# Sheet1.net
KiCad netlist of a schematic drawn in Altium Designer
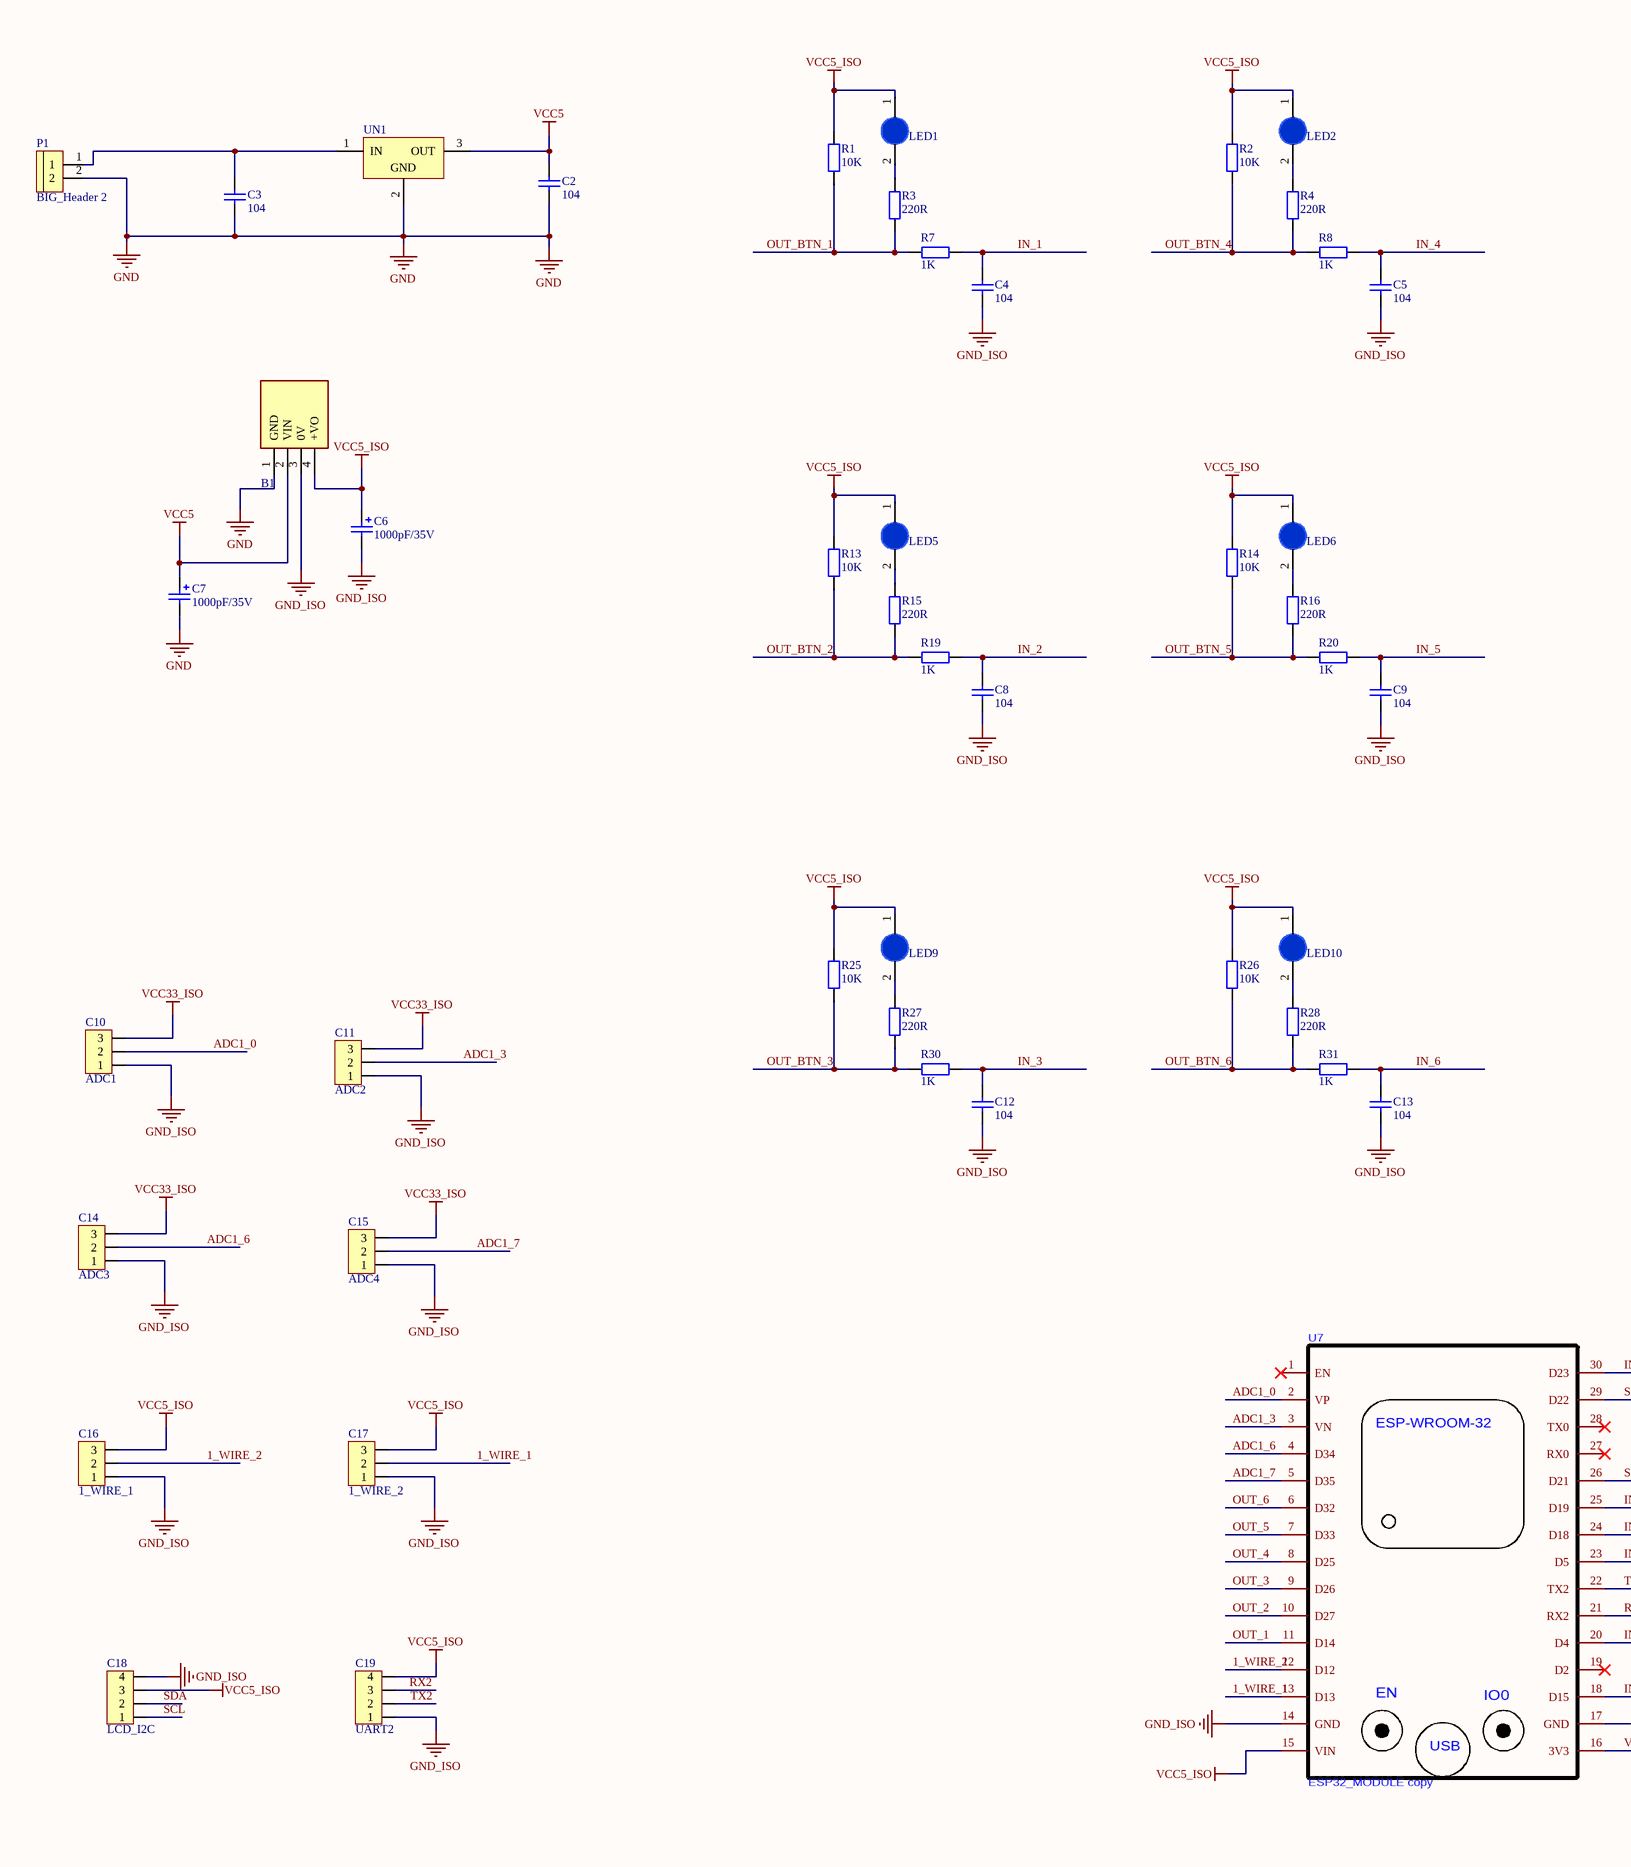
[diagram p0: Sheet1.SchDoc, left]
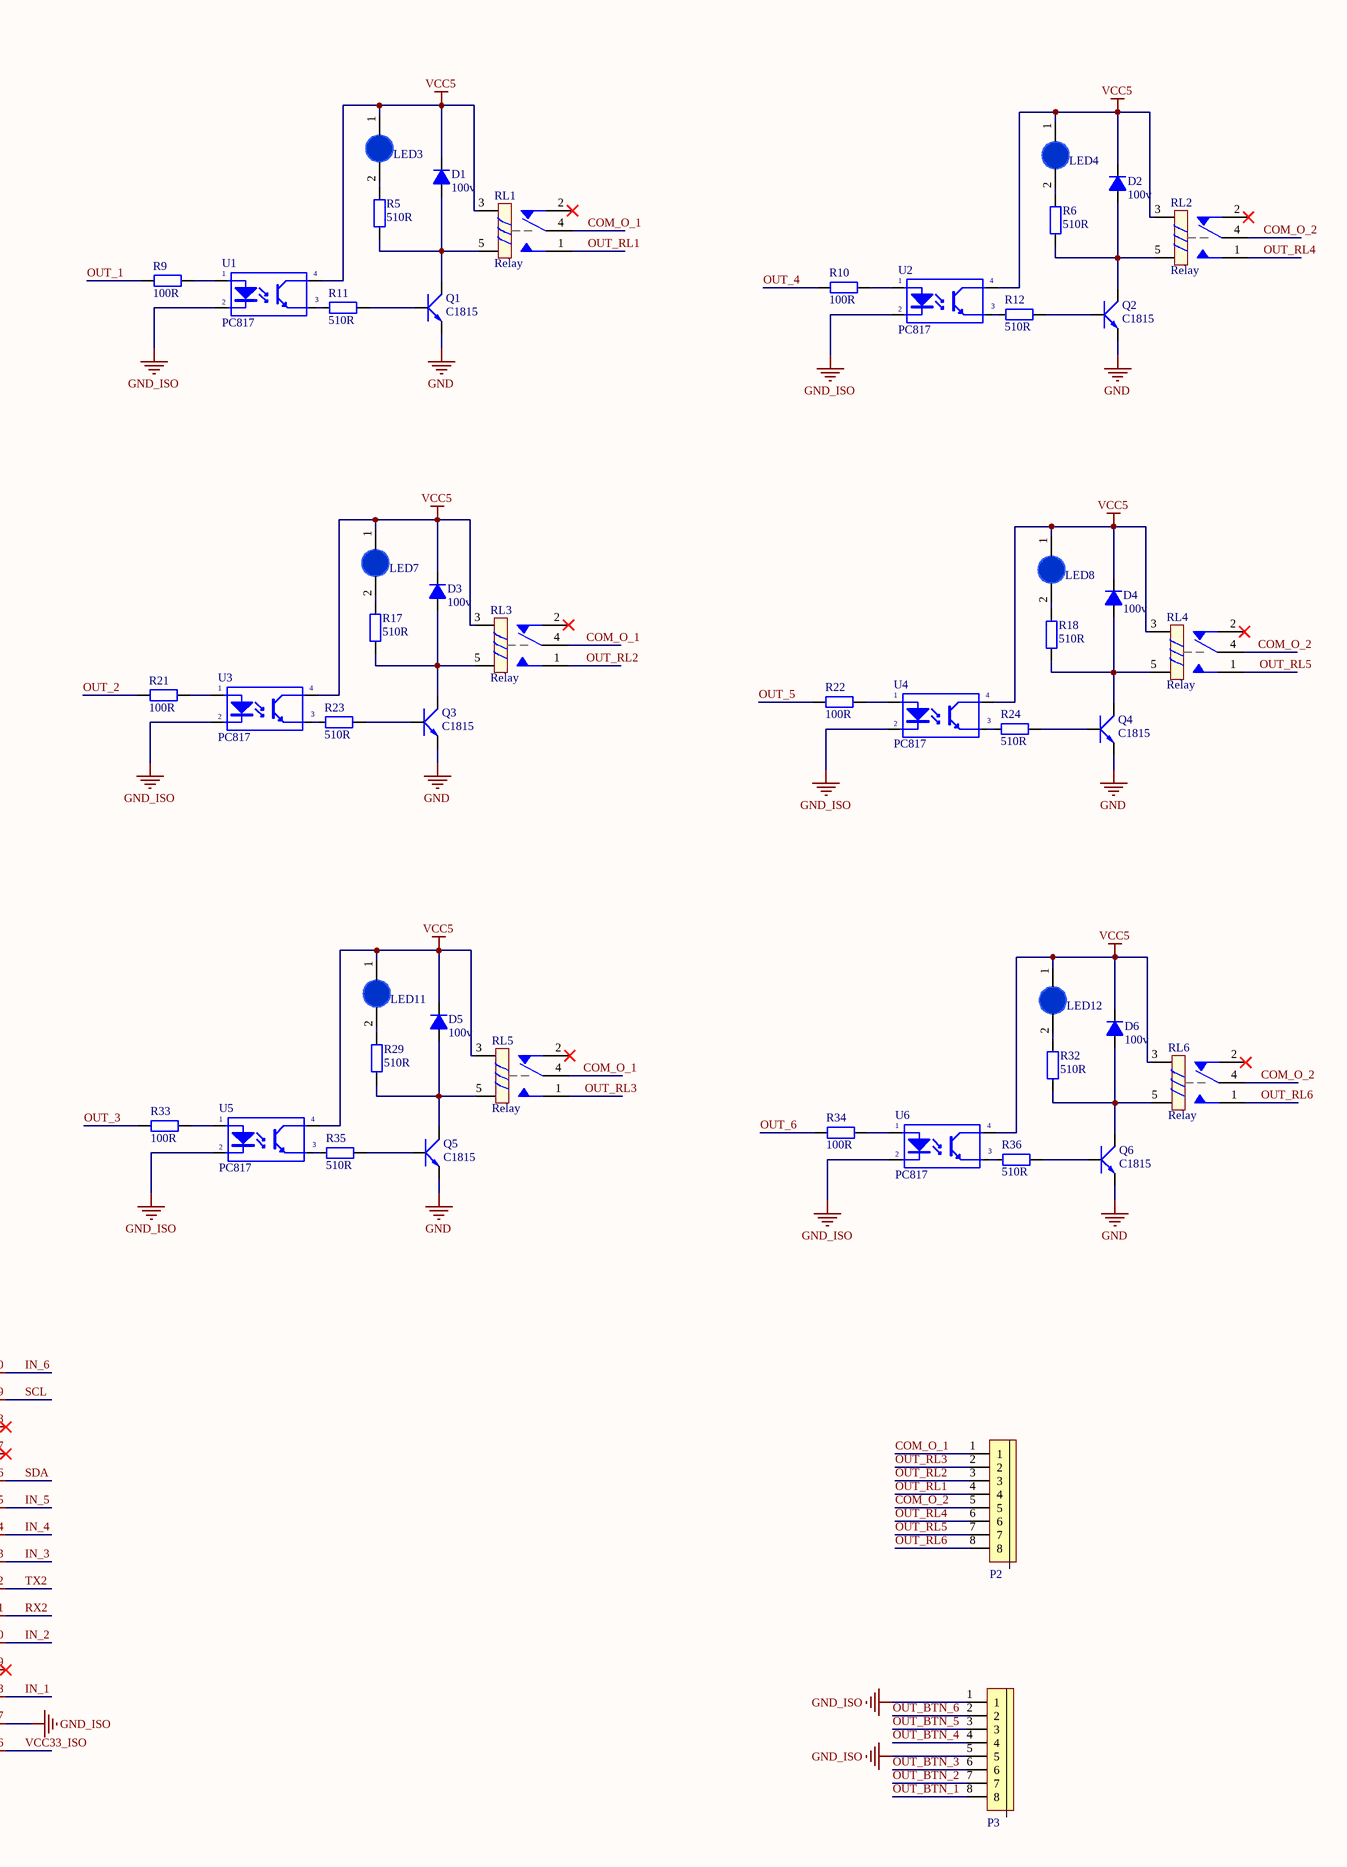
[diagram p1: Sheet1.SchDoc, right]

(export (version "E")
  (design (tool "Eeschema 10.0.6"))
  (components
    (comp (ref "B1")
      (value "B0505S1W")
      (footprint "B0505S1W")
      (description "Power Supply")
      (fields (field (name "MANUFACTURER_PART_NUMBER") "B0505S-1W"))
      (libsource (lib "myLib_v1") (part "B0505S1W"))
    )
    (comp (ref "C2")
      (value "104")
      (footprint "tu gom")
      (description "Cắm")
      (libsource (lib "Altium_Lib_by_KhueNguyenCreator") (part "Tu gom 104 50V"))
    )
    (comp (ref "C3")
      (value "104")
      (footprint "tu gom")
      (description "Cắm")
      (libsource (lib "Altium_Lib_by_KhueNguyenCreator") (part "Tu gom 104 50V"))
    )
    (comp (ref "C4")
      (value "104")
      (footprint "tu gom")
      (description "Cắm")
      (libsource (lib "Altium_Lib_by_KhueNguyenCreator") (part "Tu gom 104 50V"))
    )
    (comp (ref "C5")
      (value "104")
      (footprint "tu gom")
      (description "Cắm")
      (libsource (lib "Altium_Lib_by_KhueNguyenCreator") (part "Tu gom 104 50V"))
    )
    (comp (ref "C6")
      (value "1000pF/35V")
      (footprint "CP2/5")
      (description "Polarized Capacitor (Surface Mount)")
      (fields (field (name "Comment") "Cap Pol3") (field (name "PUBLISHER") "Altium Limited"))
      (libsource (lib "myLib_v1") (part "Cap Pol3"))
    )
    (comp (ref "C7")
      (value "1000pF/35V")
      (footprint "CP2/5")
      (description "Polarized Capacitor (Surface Mount)")
      (fields (field (name "Comment") "Cap Pol3") (field (name "PUBLISHER") "Altium Limited"))
      (libsource (lib "myLib_v1") (part "Cap Pol3"))
    )
    (comp (ref "C8")
      (value "104")
      (footprint "tu gom")
      (description "Cắm")
      (libsource (lib "Altium_Lib_by_KhueNguyenCreator") (part "Tu gom 104 50V"))
    )
    (comp (ref "C9")
      (value "104")
      (footprint "tu gom")
      (description "Cắm")
      (libsource (lib "Altium_Lib_by_KhueNguyenCreator") (part "Tu gom 104 50V"))
    )
    (comp (ref "C10")
      (value "ADC1")
      (footprint "Header3")
      (description "Header IDC, 3 x 1 Pin Vertical 2.54mm Pitch (Non-Boxed, Male)")
      (fields
        (field (name "MANUFACTURER") "Würth Elektronik eiSos GmbH")
        (field (name "PARTNO") "613002143121")
        (field (name "CREATED BY") "Karrer Zheng")
      )
      (libsource (lib "myLib_v1") (part "Header3"))
    )
    (comp (ref "C11")
      (value "ADC2")
      (footprint "Header3")
      (description "Header IDC, 3 x 1 Pin Vertical 2.54mm Pitch (Non-Boxed, Male)")
      (fields
        (field (name "MANUFACTURER") "Würth Elektronik eiSos GmbH")
        (field (name "PARTNO") "613002143121")
        (field (name "CREATED BY") "Karrer Zheng")
      )
      (libsource (lib "myLib_v1") (part "Header3"))
    )
    (comp (ref "C12")
      (value "104")
      (footprint "tu gom")
      (description "Cắm")
      (libsource (lib "Altium_Lib_by_KhueNguyenCreator") (part "Tu gom 104 50V"))
    )
    (comp (ref "C13")
      (value "104")
      (footprint "tu gom")
      (description "Cắm")
      (libsource (lib "Altium_Lib_by_KhueNguyenCreator") (part "Tu gom 104 50V"))
    )
    (comp (ref "C14")
      (value "ADC3")
      (footprint "Header3")
      (description "Header IDC, 3 x 1 Pin Vertical 2.54mm Pitch (Non-Boxed, Male)")
      (fields
        (field (name "MANUFACTURER") "Würth Elektronik eiSos GmbH")
        (field (name "PARTNO") "613002143121")
        (field (name "CREATED BY") "Karrer Zheng")
      )
      (libsource (lib "myLib_v1") (part "Header3"))
    )
    (comp (ref "C15")
      (value "ADC4")
      (footprint "Header3")
      (description "Header IDC, 3 x 1 Pin Vertical 2.54mm Pitch (Non-Boxed, Male)")
      (fields
        (field (name "MANUFACTURER") "Würth Elektronik eiSos GmbH")
        (field (name "PARTNO") "613002143121")
        (field (name "CREATED BY") "Karrer Zheng")
      )
      (libsource (lib "myLib_v1") (part "Header3"))
    )
    (comp (ref "C16")
      (value "1_WIRE_1")
      (footprint "Header3")
      (description "Header IDC, 3 x 1 Pin Vertical 2.54mm Pitch (Non-Boxed, Male)")
      (fields
        (field (name "MANUFACTURER") "Würth Elektronik eiSos GmbH")
        (field (name "PARTNO") "613002143121")
        (field (name "CREATED BY") "Karrer Zheng")
      )
      (libsource (lib "myLib_v1") (part "Header3"))
    )
    (comp (ref "C17")
      (value "1_WIRE_2")
      (footprint "Header3")
      (description "Header IDC, 3 x 1 Pin Vertical 2.54mm Pitch (Non-Boxed, Male)")
      (fields
        (field (name "MANUFACTURER") "Würth Elektronik eiSos GmbH")
        (field (name "PARTNO") "613002143121")
        (field (name "CREATED BY") "Karrer Zheng")
      )
      (libsource (lib "myLib_v1") (part "Header3"))
    )
    (comp (ref "C18")
      (value "LCD_I2C")
      (footprint "Header4")
      (description "Header IDC, 4 x 1 Pin Vertical 2.54mm Pitch (Non-Boxed, Male)")
      (fields
        (field (name "MANUFACTURER") "Würth Elektronik eiSos GmbH")
        (field (name "PARTNO") "613002143121")
        (field (name "CREATED BY") "Karrer Zheng")
      )
      (libsource (lib "myLib_v1") (part "Header4"))
    )
    (comp (ref "C19")
      (value "UART2")
      (footprint "Header4")
      (description "Header IDC, 4 x 1 Pin Vertical 2.54mm Pitch (Non-Boxed, Male)")
      (fields
        (field (name "MANUFACTURER") "Würth Elektronik eiSos GmbH")
        (field (name "PARTNO") "613002143121")
        (field (name "CREATED BY") "Karrer Zheng")
      )
      (libsource (lib "myLib_v1") (part "Header4"))
    )
    (comp (ref "D1")
      (value "100v")
      (footprint "DIODE 0.5A")
      (description "Cắm")
      (libsource (lib "Altium_Lib_by_KhueNguyenCreator") (part "Diode 1N4148"))
    )
    (comp (ref "D2")
      (value "100v")
      (footprint "DIODE 0.5A")
      (description "Cắm")
      (libsource (lib "Altium_Lib_by_KhueNguyenCreator") (part "Diode 1N4148"))
    )
    (comp (ref "D3")
      (value "100v")
      (footprint "DIODE 0.5A")
      (description "Cắm")
      (libsource (lib "Altium_Lib_by_KhueNguyenCreator") (part "Diode 1N4148"))
    )
    (comp (ref "D4")
      (value "100v")
      (footprint "DIODE 0.5A")
      (description "Cắm")
      (libsource (lib "Altium_Lib_by_KhueNguyenCreator") (part "Diode 1N4148"))
    )
    (comp (ref "D5")
      (value "100v")
      (footprint "DIODE 0.5A")
      (description "Cắm")
      (libsource (lib "Altium_Lib_by_KhueNguyenCreator") (part "Diode 1N4148"))
    )
    (comp (ref "D6")
      (value "100v")
      (footprint "DIODE 0.5A")
      (description "Cắm")
      (libsource (lib "Altium_Lib_by_KhueNguyenCreator") (part "Diode 1N4148"))
    )
    (comp (ref "LED1")
      (value "LED 3mm")
      (footprint "LED-3MM-BLUE")
      (description "Cắm")
      (libsource (lib "myLib_v1") (part "LED 3mm Xanh Duong"))
    )
    (comp (ref "LED2")
      (value "LED 3mm")
      (footprint "LED-3MM-BLUE")
      (description "Cắm")
      (libsource (lib "myLib_v1") (part "LED 3mm Xanh Duong"))
    )
    (comp (ref "LED3")
      (value "LED 3mm")
      (footprint "LED-3MM-BLUE")
      (description "Cắm")
      (libsource (lib "myLib_v1") (part "LED 3mm Xanh Duong"))
    )
    (comp (ref "LED4")
      (value "LED 3mm")
      (footprint "LED-3MM-BLUE")
      (description "Cắm")
      (libsource (lib "myLib_v1") (part "LED 3mm Xanh Duong"))
    )
    (comp (ref "LED5")
      (value "LED 3mm")
      (footprint "LED-3MM-BLUE")
      (description "Cắm")
      (libsource (lib "myLib_v1") (part "LED 3mm Xanh Duong"))
    )
    (comp (ref "LED6")
      (value "LED 3mm")
      (footprint "LED-3MM-BLUE")
      (description "Cắm")
      (libsource (lib "myLib_v1") (part "LED 3mm Xanh Duong"))
    )
    (comp (ref "LED7")
      (value "LED 3mm")
      (footprint "LED-3MM-BLUE")
      (description "Cắm")
      (libsource (lib "myLib_v1") (part "LED 3mm Xanh Duong"))
    )
    (comp (ref "LED8")
      (value "LED 3mm")
      (footprint "LED-3MM-BLUE")
      (description "Cắm")
      (libsource (lib "myLib_v1") (part "LED 3mm Xanh Duong"))
    )
    (comp (ref "LED9")
      (value "LED 3mm")
      (footprint "LED-3MM-BLUE")
      (description "Cắm")
      (libsource (lib "myLib_v1") (part "LED 3mm Xanh Duong"))
    )
    (comp (ref "LED10")
      (value "LED 3mm")
      (footprint "LED-3MM-BLUE")
      (description "Cắm")
      (libsource (lib "myLib_v1") (part "LED 3mm Xanh Duong"))
    )
    (comp (ref "LED11")
      (value "LED 3mm")
      (footprint "LED-3MM-BLUE")
      (description "Cắm")
      (libsource (lib "myLib_v1") (part "LED 3mm Xanh Duong"))
    )
    (comp (ref "LED12")
      (value "LED 3mm")
      (footprint "LED-3MM-BLUE")
      (description "Cắm")
      (libsource (lib "myLib_v1") (part "LED 3mm Xanh Duong"))
    )
    (comp (ref "P1")
      (value "BIG_Header 2")
      (footprint "BIG_Header 2")
      (libsource (lib "BYTECH_HW_LIB_2019 (1)") (part "BIG_Header 2"))
    )
    (comp (ref "P2")
      (value "BIG Heager 8")
      (footprint "BIG_Header 8")
      (libsource (lib "BYTECH_HW_LIB_2019 (1)") (part "BIG_Header 8"))
    )
    (comp (ref "P3")
      (value "BIG Heager 8")
      (footprint "BIG_Header 8")
      (libsource (lib "BYTECH_HW_LIB_2019 (1)") (part "BIG_Header 8"))
    )
    (comp (ref "Q1")
      (value "C1815")
      (footprint "C1815_cam")
      (description "NPN 600mW, ECB")
      (libsource (lib "myLib_v1") (part "C1815"))
    )
    (comp (ref "Q2")
      (value "C1815")
      (footprint "C1815_cam")
      (description "NPN 600mW, ECB")
      (libsource (lib "myLib_v1") (part "C1815"))
    )
    (comp (ref "Q3")
      (value "C1815")
      (footprint "C1815_cam")
      (description "NPN 600mW, ECB")
      (libsource (lib "myLib_v1") (part "C1815"))
    )
    (comp (ref "Q4")
      (value "C1815")
      (footprint "C1815_cam")
      (description "NPN 600mW, ECB")
      (libsource (lib "myLib_v1") (part "C1815"))
    )
    (comp (ref "Q5")
      (value "C1815")
      (footprint "C1815_cam")
      (description "NPN 600mW, ECB")
      (libsource (lib "myLib_v1") (part "C1815"))
    )
    (comp (ref "Q6")
      (value "C1815")
      (footprint "C1815_cam")
      (description "NPN 600mW, ECB")
      (libsource (lib "myLib_v1") (part "C1815"))
    )
    (comp (ref "R1")
      (value "10K")
      (footprint "R1/4W")
      (description "Resistor 1/4W")
      (libsource (lib "myLib_v1") (part "R1/4W"))
    )
    (comp (ref "R2")
      (value "10K")
      (footprint "R1/4W")
      (description "Resistor 1/4W")
      (libsource (lib "myLib_v1") (part "R1/4W"))
    )
    (comp (ref "R3")
      (value "220R")
      (footprint "R1/4W")
      (description "Resistor 1/4W")
      (libsource (lib "myLib_v1") (part "R1/4W"))
    )
    (comp (ref "R4")
      (value "220R")
      (footprint "R1/4W")
      (description "Resistor 1/4W")
      (libsource (lib "myLib_v1") (part "R1/4W"))
    )
    (comp (ref "R5")
      (value "510R")
      (footprint "R1/4W")
      (description "Resistor 1/4W")
      (libsource (lib "myLib_v1") (part "R1/4W"))
    )
    (comp (ref "R6")
      (value "510R")
      (footprint "R1/4W")
      (description "Resistor 1/4W")
      (libsource (lib "myLib_v1") (part "R1/4W"))
    )
    (comp (ref "R7")
      (value "1K")
      (footprint "R1/4W")
      (description "Resistor 1/4W")
      (libsource (lib "myLib_v1") (part "R1/4W"))
    )
    (comp (ref "R8")
      (value "1K")
      (footprint "R1/4W")
      (description "Resistor 1/4W")
      (libsource (lib "myLib_v1") (part "R1/4W"))
    )
    (comp (ref "R9")
      (value "100R")
      (footprint "R1/4W")
      (description "Resistor 1/4W")
      (libsource (lib "myLib_v1") (part "R1/4W"))
    )
    (comp (ref "R10")
      (value "100R")
      (footprint "R1/4W")
      (description "Resistor 1/4W")
      (libsource (lib "myLib_v1") (part "R1/4W"))
    )
    (comp (ref "R11")
      (value "510R")
      (footprint "R1/4W")
      (description "Resistor 1/4W")
      (libsource (lib "myLib_v1") (part "R1/4W"))
    )
    (comp (ref "R12")
      (value "510R")
      (footprint "R1/4W")
      (description "Resistor 1/4W")
      (libsource (lib "myLib_v1") (part "R1/4W"))
    )
    (comp (ref "R13")
      (value "10K")
      (footprint "R1/4W")
      (description "Resistor 1/4W")
      (libsource (lib "myLib_v1") (part "R1/4W"))
    )
    (comp (ref "R14")
      (value "10K")
      (footprint "R1/4W")
      (description "Resistor 1/4W")
      (libsource (lib "myLib_v1") (part "R1/4W"))
    )
    (comp (ref "R15")
      (value "220R")
      (footprint "R1/4W")
      (description "Resistor 1/4W")
      (libsource (lib "myLib_v1") (part "R1/4W"))
    )
    (comp (ref "R16")
      (value "220R")
      (footprint "R1/4W")
      (description "Resistor 1/4W")
      (libsource (lib "myLib_v1") (part "R1/4W"))
    )
    (comp (ref "R17")
      (value "510R")
      (footprint "R1/4W")
      (description "Resistor 1/4W")
      (libsource (lib "myLib_v1") (part "R1/4W"))
    )
    (comp (ref "R18")
      (value "510R")
      (footprint "R1/4W")
      (description "Resistor 1/4W")
      (libsource (lib "myLib_v1") (part "R1/4W"))
    )
    (comp (ref "R19")
      (value "1K")
      (footprint "R1/4W")
      (description "Resistor 1/4W")
      (libsource (lib "myLib_v1") (part "R1/4W"))
    )
    (comp (ref "R20")
      (value "1K")
      (footprint "R1/4W")
      (description "Resistor 1/4W")
      (libsource (lib "myLib_v1") (part "R1/4W"))
    )
    (comp (ref "R21")
      (value "100R")
      (footprint "R1/4W")
      (description "Resistor 1/4W")
      (libsource (lib "myLib_v1") (part "R1/4W"))
    )
    (comp (ref "R22")
      (value "100R")
      (footprint "R1/4W")
      (description "Resistor 1/4W")
      (libsource (lib "myLib_v1") (part "R1/4W"))
    )
    (comp (ref "R23")
      (value "510R")
      (footprint "R1/4W")
      (description "Resistor 1/4W")
      (libsource (lib "myLib_v1") (part "R1/4W"))
    )
    (comp (ref "R24")
      (value "510R")
      (footprint "R1/4W")
      (description "Resistor 1/4W")
      (libsource (lib "myLib_v1") (part "R1/4W"))
    )
    (comp (ref "R25")
      (value "10K")
      (footprint "R1/4W")
      (description "Resistor 1/4W")
      (libsource (lib "myLib_v1") (part "R1/4W"))
    )
    (comp (ref "R26")
      (value "10K")
      (footprint "R1/4W")
      (description "Resistor 1/4W")
      (libsource (lib "myLib_v1") (part "R1/4W"))
    )
    (comp (ref "R27")
      (value "220R")
      (footprint "R1/4W")
      (description "Resistor 1/4W")
      (libsource (lib "myLib_v1") (part "R1/4W"))
    )
    (comp (ref "R28")
      (value "220R")
      (footprint "R1/4W")
      (description "Resistor 1/4W")
      (libsource (lib "myLib_v1") (part "R1/4W"))
    )
    (comp (ref "R29")
      (value "510R")
      (footprint "R1/4W")
      (description "Resistor 1/4W")
      (libsource (lib "myLib_v1") (part "R1/4W"))
    )
    (comp (ref "R30")
      (value "1K")
      (footprint "R1/4W")
      (description "Resistor 1/4W")
      (libsource (lib "myLib_v1") (part "R1/4W"))
    )
    (comp (ref "R31")
      (value "1K")
      (footprint "R1/4W")
      (description "Resistor 1/4W")
      (libsource (lib "myLib_v1") (part "R1/4W"))
    )
    (comp (ref "R32")
      (value "510R")
      (footprint "R1/4W")
      (description "Resistor 1/4W")
      (libsource (lib "myLib_v1") (part "R1/4W"))
    )
    (comp (ref "R33")
      (value "100R")
      (footprint "R1/4W")
      (description "Resistor 1/4W")
      (libsource (lib "myLib_v1") (part "R1/4W"))
    )
    (comp (ref "R34")
      (value "100R")
      (footprint "R1/4W")
      (description "Resistor 1/4W")
      (libsource (lib "myLib_v1") (part "R1/4W"))
    )
    (comp (ref "R35")
      (value "510R")
      (footprint "R1/4W")
      (description "Resistor 1/4W")
      (libsource (lib "myLib_v1") (part "R1/4W"))
    )
    (comp (ref "R36")
      (value "510R")
      (footprint "R1/4W")
      (description "Resistor 1/4W")
      (libsource (lib "myLib_v1") (part "R1/4W"))
    )
    (comp (ref "RL1")
      (value "Relay")
      (footprint "RELAY_SRA_05VDC_SL_C")
      (description "Relay 5 Chan")
      (libsource (lib "myLib_v1") (part "RL_SRA-05VDC-SL-C"))
    )
    (comp (ref "RL2")
      (value "Relay")
      (footprint "RELAY_SRA_05VDC_SL_C")
      (description "Relay 5 Chan")
      (libsource (lib "myLib_v1") (part "RL_SRA-05VDC-SL-C"))
    )
    (comp (ref "RL3")
      (value "Relay")
      (footprint "RELAY_SRA_05VDC_SL_C")
      (description "Relay 5 Chan")
      (libsource (lib "myLib_v1") (part "RL_SRA-05VDC-SL-C"))
    )
    (comp (ref "RL4")
      (value "Relay")
      (footprint "RELAY_SRA_05VDC_SL_C")
      (description "Relay 5 Chan")
      (libsource (lib "myLib_v1") (part "RL_SRA-05VDC-SL-C"))
    )
    (comp (ref "RL5")
      (value "Relay")
      (footprint "RELAY_SRA_05VDC_SL_C")
      (description "Relay 5 Chan")
      (libsource (lib "myLib_v1") (part "RL_SRA-05VDC-SL-C"))
    )
    (comp (ref "RL6")
      (value "Relay")
      (footprint "RELAY_SRA_05VDC_SL_C")
      (description "Relay 5 Chan")
      (libsource (lib "myLib_v1") (part "RL_SRA-05VDC-SL-C"))
    )
    (comp (ref "U1")
      (value "PC817")
      (footprint "DIP4/W0.3")
      (description "Single Opto")
      (libsource (lib "myLib_v1") (part "PC817"))
    )
    (comp (ref "U2")
      (value "PC817")
      (footprint "DIP4/W0.3")
      (description "Single Opto")
      (libsource (lib "myLib_v1") (part "PC817"))
    )
    (comp (ref "U3")
      (value "PC817")
      (footprint "DIP4/W0.3")
      (description "Single Opto")
      (libsource (lib "myLib_v1") (part "PC817"))
    )
    (comp (ref "U4")
      (value "PC817")
      (footprint "DIP4/W0.3")
      (description "Single Opto")
      (libsource (lib "myLib_v1") (part "PC817"))
    )
    (comp (ref "U5")
      (value "PC817")
      (footprint "DIP4/W0.3")
      (description "Single Opto")
      (libsource (lib "myLib_v1") (part "PC817"))
    )
    (comp (ref "U6")
      (value "PC817")
      (footprint "DIP4/W0.3")
      (description "Single Opto")
      (libsource (lib "myLib_v1") (part "PC817"))
    )
    (comp (ref "U7")
      (value "ESP32_MODULE copy")
      (footprint "ESP32-WIFIMODULE-FOOTPRINT")
      (libsource (lib "myLib_v1") (part "ESP32_MODULE copy"))
    )
    (comp (ref "UN1")
      (value "L78M05CP")
      (footprint "QTO-220H2")
      (description "Positive Voltage Regulator")
      (fields (field (name "PUBLISHER") "Altium Limited"))
      (libsource (lib "syhaunguyen") (part "L78M05CP"))
    )
  )
  (nets
    (net (code "1") (name "/1_WIRE_1") (class "Default")
      (node (ref "C17") (pin "2") (pinfunction "2_2") (pintype "passive"))
      (node (ref "U7") (pin "13") (pinfunction "D13_13") (pintype "passive"))
    )
    (net (code "2") (name "/1_WIRE_2") (class "Default")
      (node (ref "C16") (pin "2") (pinfunction "2_2") (pintype "passive"))
      (node (ref "U7") (pin "12") (pinfunction "D12_12") (pintype "passive"))
    )
    (net (code "3") (name "/ADC1_0") (class "Default")
      (node (ref "C10") (pin "2") (pinfunction "2_2") (pintype "passive"))
      (node (ref "U7") (pin "2") (pinfunction "VP_2") (pintype "passive"))
    )
    (net (code "4") (name "/ADC1_3") (class "Default")
      (node (ref "C11") (pin "2") (pinfunction "2_2") (pintype "passive"))
      (node (ref "U7") (pin "3") (pinfunction "VN_3") (pintype "passive"))
    )
    (net (code "5") (name "/ADC1_6") (class "Default")
      (node (ref "C14") (pin "2") (pinfunction "2_2") (pintype "passive"))
      (node (ref "U7") (pin "4") (pinfunction "D34_4") (pintype "passive"))
    )
    (net (code "6") (name "/ADC1_7") (class "Default")
      (node (ref "C15") (pin "2") (pinfunction "2_2") (pintype "passive"))
      (node (ref "U7") (pin "5") (pinfunction "D35_5") (pintype "passive"))
    )
    (net (code "7") (name "/COM_O_1") (class "Default")
      (node (ref "P2") (pin "1") (pinfunction "1_1") (pintype "passive"))
      (node (ref "RL1") (pin "4") (pinfunction "4_4") (pintype "passive"))
      (node (ref "RL3") (pin "4") (pinfunction "4_4") (pintype "passive"))
      (node (ref "RL5") (pin "4") (pinfunction "4_4") (pintype "passive"))
    )
    (net (code "8") (name "/COM_O_2") (class "Default")
      (node (ref "P2") (pin "5") (pinfunction "5_5") (pintype "passive"))
      (node (ref "RL2") (pin "4") (pinfunction "4_4") (pintype "passive"))
      (node (ref "RL4") (pin "4") (pinfunction "4_4") (pintype "passive"))
      (node (ref "RL6") (pin "4") (pinfunction "4_4") (pintype "passive"))
    )
    (net (code "9") (name "/IN_1") (class "Default")
      (node (ref "C4") (pin "1") (pinfunction "1_1") (pintype "passive"))
      (node (ref "R7") (pin "1") (pinfunction "1_1") (pintype "passive"))
      (node (ref "U7") (pin "18") (pinfunction "D15_18") (pintype "passive"))
    )
    (net (code "10") (name "/IN_2") (class "Default")
      (node (ref "C8") (pin "1") (pinfunction "1_1") (pintype "passive"))
      (node (ref "R19") (pin "1") (pinfunction "1_1") (pintype "passive"))
      (node (ref "U7") (pin "20") (pinfunction "D4_20") (pintype "passive"))
    )
    (net (code "11") (name "/IN_3") (class "Default")
      (node (ref "C12") (pin "1") (pinfunction "1_1") (pintype "passive"))
      (node (ref "R30") (pin "1") (pinfunction "1_1") (pintype "passive"))
      (node (ref "U7") (pin "23") (pinfunction "D5_23") (pintype "passive"))
    )
    (net (code "12") (name "/IN_4") (class "Default")
      (node (ref "C5") (pin "1") (pinfunction "1_1") (pintype "passive"))
      (node (ref "R8") (pin "1") (pinfunction "1_1") (pintype "passive"))
      (node (ref "U7") (pin "24") (pinfunction "D18_24") (pintype "passive"))
    )
    (net (code "13") (name "/IN_5") (class "Default")
      (node (ref "C9") (pin "1") (pinfunction "1_1") (pintype "passive"))
      (node (ref "R20") (pin "1") (pinfunction "1_1") (pintype "passive"))
      (node (ref "U7") (pin "25") (pinfunction "D19_25") (pintype "passive"))
    )
    (net (code "14") (name "/IN_6") (class "Default")
      (node (ref "C13") (pin "1") (pinfunction "1_1") (pintype "passive"))
      (node (ref "R31") (pin "1") (pinfunction "1_1") (pintype "passive"))
      (node (ref "U7") (pin "30") (pinfunction "D23_30") (pintype "passive"))
    )
    (net (code "15") (name "/OUT_1") (class "Default")
      (node (ref "R9") (pin "1") (pinfunction "1_1") (pintype "passive"))
      (node (ref "U7") (pin "11") (pinfunction "D14_11") (pintype "passive"))
    )
    (net (code "16") (name "/OUT_2") (class "Default")
      (node (ref "R21") (pin "1") (pinfunction "1_1") (pintype "passive"))
      (node (ref "U7") (pin "10") (pinfunction "D27_10") (pintype "passive"))
    )
    (net (code "17") (name "/OUT_3") (class "Default")
      (node (ref "R33") (pin "1") (pinfunction "1_1") (pintype "passive"))
      (node (ref "U7") (pin "9") (pinfunction "D26_9") (pintype "passive"))
    )
    (net (code "18") (name "/OUT_4") (class "Default")
      (node (ref "R10") (pin "1") (pinfunction "1_1") (pintype "passive"))
      (node (ref "U7") (pin "8") (pinfunction "D25_8") (pintype "passive"))
    )
    (net (code "19") (name "/OUT_5") (class "Default")
      (node (ref "R22") (pin "1") (pinfunction "1_1") (pintype "passive"))
      (node (ref "U7") (pin "7") (pinfunction "D33_7") (pintype "passive"))
    )
    (net (code "20") (name "/OUT_6") (class "Default")
      (node (ref "R34") (pin "1") (pinfunction "1_1") (pintype "passive"))
      (node (ref "U7") (pin "6") (pinfunction "D32_6") (pintype "passive"))
    )
    (net (code "21") (name "/OUT_BTN_1") (class "Default")
      (node (ref "P3") (pin "8") (pinfunction "8_8") (pintype "passive"))
      (node (ref "R1") (pin "1") (pinfunction "1_1") (pintype "passive"))
      (node (ref "R3") (pin "1") (pinfunction "1_1") (pintype "passive"))
      (node (ref "R7") (pin "2") (pinfunction "2_2") (pintype "passive"))
    )
    (net (code "22") (name "/OUT_BTN_2") (class "Default")
      (node (ref "P3") (pin "7") (pinfunction "7_7") (pintype "passive"))
      (node (ref "R13") (pin "1") (pinfunction "1_1") (pintype "passive"))
      (node (ref "R15") (pin "1") (pinfunction "1_1") (pintype "passive"))
      (node (ref "R19") (pin "2") (pinfunction "2_2") (pintype "passive"))
    )
    (net (code "23") (name "/OUT_BTN_3") (class "Default")
      (node (ref "P3") (pin "6") (pinfunction "6_6") (pintype "passive"))
      (node (ref "R25") (pin "1") (pinfunction "1_1") (pintype "passive"))
      (node (ref "R27") (pin "1") (pinfunction "1_1") (pintype "passive"))
      (node (ref "R30") (pin "2") (pinfunction "2_2") (pintype "passive"))
    )
    (net (code "24") (name "/OUT_BTN_4") (class "Default")
      (node (ref "P3") (pin "4") (pinfunction "4_4") (pintype "passive"))
      (node (ref "R2") (pin "1") (pinfunction "1_1") (pintype "passive"))
      (node (ref "R4") (pin "1") (pinfunction "1_1") (pintype "passive"))
      (node (ref "R8") (pin "2") (pinfunction "2_2") (pintype "passive"))
    )
    (net (code "25") (name "/OUT_BTN_5") (class "Default")
      (node (ref "P3") (pin "3") (pinfunction "3_3") (pintype "passive"))
      (node (ref "R14") (pin "1") (pinfunction "1_1") (pintype "passive"))
      (node (ref "R16") (pin "1") (pinfunction "1_1") (pintype "passive"))
      (node (ref "R20") (pin "2") (pinfunction "2_2") (pintype "passive"))
    )
    (net (code "26") (name "/OUT_BTN_6") (class "Default")
      (node (ref "P3") (pin "2") (pinfunction "2_2") (pintype "passive"))
      (node (ref "R26") (pin "1") (pinfunction "1_1") (pintype "passive"))
      (node (ref "R28") (pin "1") (pinfunction "1_1") (pintype "passive"))
      (node (ref "R31") (pin "2") (pinfunction "2_2") (pintype "passive"))
    )
    (net (code "27") (name "/OUT_RL1") (class "Default")
      (node (ref "P2") (pin "4") (pinfunction "4_4") (pintype "passive"))
      (node (ref "RL1") (pin "1") (pinfunction "1_1") (pintype "passive"))
    )
    (net (code "28") (name "/OUT_RL2") (class "Default")
      (node (ref "P2") (pin "3") (pinfunction "3_3") (pintype "passive"))
      (node (ref "RL3") (pin "1") (pinfunction "1_1") (pintype "passive"))
    )
    (net (code "29") (name "/OUT_RL3") (class "Default")
      (node (ref "P2") (pin "2") (pinfunction "2_2") (pintype "passive"))
      (node (ref "RL5") (pin "1") (pinfunction "1_1") (pintype "passive"))
    )
    (net (code "30") (name "/OUT_RL4") (class "Default")
      (node (ref "P2") (pin "6") (pinfunction "6_6") (pintype "passive"))
      (node (ref "RL2") (pin "1") (pinfunction "1_1") (pintype "passive"))
    )
    (net (code "31") (name "/OUT_RL5") (class "Default")
      (node (ref "P2") (pin "7") (pinfunction "7_7") (pintype "passive"))
      (node (ref "RL4") (pin "1") (pinfunction "1_1") (pintype "passive"))
    )
    (net (code "32") (name "/OUT_RL6") (class "Default")
      (node (ref "P2") (pin "8") (pinfunction "8_8") (pintype "passive"))
      (node (ref "RL6") (pin "1") (pinfunction "1_1") (pintype "passive"))
    )
    (net (code "33") (name "/RX2") (class "Default")
      (node (ref "C19") (pin "3") (pinfunction "3_3") (pintype "passive"))
      (node (ref "U7") (pin "21") (pinfunction "RX2_21") (pintype "passive"))
    )
    (net (code "34") (name "/SCL") (class "Default")
      (node (ref "C18") (pin "1") (pinfunction "1_1") (pintype "passive"))
      (node (ref "U7") (pin "29") (pinfunction "D22_29") (pintype "passive"))
    )
    (net (code "35") (name "/SDA") (class "Default")
      (node (ref "C18") (pin "2") (pinfunction "2_2") (pintype "passive"))
      (node (ref "U7") (pin "26") (pinfunction "D21_26") (pintype "passive"))
    )
    (net (code "36") (name "/TX2") (class "Default")
      (node (ref "C19") (pin "2") (pinfunction "2_2") (pintype "passive"))
      (node (ref "U7") (pin "22") (pinfunction "TX2_22") (pintype "passive"))
    )
    (net (code "37") (name "GND") (class "Default")
      (node (ref "B1") (pin "1") (pinfunction "GND_1") (pintype "passive"))
      (node (ref "C2") (pin "2") (pinfunction "2_2") (pintype "passive"))
      (node (ref "C3") (pin "2") (pinfunction "2_2") (pintype "passive"))
      (node (ref "C7") (pin "2") (pinfunction "2_2") (pintype "passive"))
      (node (ref "P1") (pin "2") (pinfunction "2_2") (pintype "passive"))
      (node (ref "Q1") (pin "1") (pinfunction "E_1") (pintype "passive"))
      (node (ref "Q2") (pin "1") (pinfunction "E_1") (pintype "passive"))
      (node (ref "Q3") (pin "1") (pinfunction "E_1") (pintype "passive"))
      (node (ref "Q4") (pin "1") (pinfunction "E_1") (pintype "passive"))
      (node (ref "Q5") (pin "1") (pinfunction "E_1") (pintype "passive"))
      (node (ref "Q6") (pin "1") (pinfunction "E_1") (pintype "passive"))
      (node (ref "UN1") (pin "2") (pinfunction "GND_2") (pintype "power_in"))
    )
    (net (code "38") (name "GND_ISO") (class "Default")
      (node (ref "B1") (pin "3") (pinfunction "0V_3") (pintype "passive"))
      (node (ref "C10") (pin "1") (pinfunction "1_1") (pintype "passive"))
      (node (ref "C11") (pin "1") (pinfunction "1_1") (pintype "passive"))
      (node (ref "C12") (pin "2") (pinfunction "2_2") (pintype "passive"))
      (node (ref "C13") (pin "2") (pinfunction "2_2") (pintype "passive"))
      (node (ref "C14") (pin "1") (pinfunction "1_1") (pintype "passive"))
      (node (ref "C15") (pin "1") (pinfunction "1_1") (pintype "passive"))
      (node (ref "C16") (pin "1") (pinfunction "1_1") (pintype "passive"))
      (node (ref "C17") (pin "1") (pinfunction "1_1") (pintype "passive"))
      (node (ref "C18") (pin "4") (pinfunction "4_4") (pintype "passive"))
      (node (ref "C19") (pin "1") (pinfunction "1_1") (pintype "passive"))
      (node (ref "C4") (pin "2") (pinfunction "2_2") (pintype "passive"))
      (node (ref "C5") (pin "2") (pinfunction "2_2") (pintype "passive"))
      (node (ref "C6") (pin "2") (pinfunction "2_2") (pintype "passive"))
      (node (ref "C8") (pin "2") (pinfunction "2_2") (pintype "passive"))
      (node (ref "C9") (pin "2") (pinfunction "2_2") (pintype "passive"))
      (node (ref "P3") (pin "1") (pinfunction "1_1") (pintype "passive"))
      (node (ref "P3") (pin "5") (pinfunction "5_5") (pintype "passive"))
      (node (ref "U1") (pin "2") (pinfunction "K_2") (pintype "passive"))
      (node (ref "U2") (pin "2") (pinfunction "K_2") (pintype "passive"))
      (node (ref "U3") (pin "2") (pinfunction "K_2") (pintype "passive"))
      (node (ref "U4") (pin "2") (pinfunction "K_2") (pintype "passive"))
      (node (ref "U5") (pin "2") (pinfunction "K_2") (pintype "passive"))
      (node (ref "U6") (pin "2") (pinfunction "K_2") (pintype "passive"))
      (node (ref "U7") (pin "14") (pinfunction "GND_14") (pintype "passive"))
      (node (ref "U7") (pin "17") (pinfunction "GND_17") (pintype "passive"))
    )
    (net (code "39") (name "Net-(D1-A)") (class "Default")
      (node (ref "D1") (pin "1") (pinfunction "A_1") (pintype "passive"))
      (node (ref "Q1") (pin "2") (pinfunction "C_2") (pintype "passive"))
      (node (ref "R5") (pin "2") (pinfunction "2_2") (pintype "passive"))
      (node (ref "RL1") (pin "5") (pinfunction "5_5") (pintype "passive"))
    )
    (net (code "40") (name "Net-(D2-A)") (class "Default")
      (node (ref "D2") (pin "1") (pinfunction "A_1") (pintype "passive"))
      (node (ref "Q2") (pin "2") (pinfunction "C_2") (pintype "passive"))
      (node (ref "R6") (pin "2") (pinfunction "2_2") (pintype "passive"))
      (node (ref "RL2") (pin "5") (pinfunction "5_5") (pintype "passive"))
    )
    (net (code "41") (name "Net-(D3-A)") (class "Default")
      (node (ref "D3") (pin "1") (pinfunction "A_1") (pintype "passive"))
      (node (ref "Q3") (pin "2") (pinfunction "C_2") (pintype "passive"))
      (node (ref "R17") (pin "2") (pinfunction "2_2") (pintype "passive"))
      (node (ref "RL3") (pin "5") (pinfunction "5_5") (pintype "passive"))
    )
    (net (code "42") (name "Net-(D4-A)") (class "Default")
      (node (ref "D4") (pin "1") (pinfunction "A_1") (pintype "passive"))
      (node (ref "Q4") (pin "2") (pinfunction "C_2") (pintype "passive"))
      (node (ref "R18") (pin "2") (pinfunction "2_2") (pintype "passive"))
      (node (ref "RL4") (pin "5") (pinfunction "5_5") (pintype "passive"))
    )
    (net (code "43") (name "Net-(D5-A)") (class "Default")
      (node (ref "D5") (pin "1") (pinfunction "A_1") (pintype "passive"))
      (node (ref "Q5") (pin "2") (pinfunction "C_2") (pintype "passive"))
      (node (ref "R29") (pin "2") (pinfunction "2_2") (pintype "passive"))
      (node (ref "RL5") (pin "5") (pinfunction "5_5") (pintype "passive"))
    )
    (net (code "44") (name "Net-(D6-A)") (class "Default")
      (node (ref "D6") (pin "1") (pinfunction "A_1") (pintype "passive"))
      (node (ref "Q6") (pin "2") (pinfunction "C_2") (pintype "passive"))
      (node (ref "R32") (pin "2") (pinfunction "2_2") (pintype "passive"))
      (node (ref "RL6") (pin "5") (pinfunction "5_5") (pintype "passive"))
    )
    (net (code "45") (name "Net-(LED1-K)") (class "Default")
      (node (ref "LED1") (pin "2") (pinfunction "K_2") (pintype "passive"))
      (node (ref "R3") (pin "2") (pinfunction "2_2") (pintype "passive"))
    )
    (net (code "46") (name "Net-(LED2-K)") (class "Default")
      (node (ref "LED2") (pin "2") (pinfunction "K_2") (pintype "passive"))
      (node (ref "R4") (pin "2") (pinfunction "2_2") (pintype "passive"))
    )
    (net (code "47") (name "Net-(LED3-K)") (class "Default")
      (node (ref "LED3") (pin "2") (pinfunction "K_2") (pintype "passive"))
      (node (ref "R5") (pin "1") (pinfunction "1_1") (pintype "passive"))
    )
    (net (code "48") (name "Net-(LED4-K)") (class "Default")
      (node (ref "LED4") (pin "2") (pinfunction "K_2") (pintype "passive"))
      (node (ref "R6") (pin "1") (pinfunction "1_1") (pintype "passive"))
    )
    (net (code "49") (name "Net-(LED5-K)") (class "Default")
      (node (ref "LED5") (pin "2") (pinfunction "K_2") (pintype "passive"))
      (node (ref "R15") (pin "2") (pinfunction "2_2") (pintype "passive"))
    )
    (net (code "50") (name "Net-(LED6-K)") (class "Default")
      (node (ref "LED6") (pin "2") (pinfunction "K_2") (pintype "passive"))
      (node (ref "R16") (pin "2") (pinfunction "2_2") (pintype "passive"))
    )
    (net (code "51") (name "Net-(LED7-K)") (class "Default")
      (node (ref "LED7") (pin "2") (pinfunction "K_2") (pintype "passive"))
      (node (ref "R17") (pin "1") (pinfunction "1_1") (pintype "passive"))
    )
    (net (code "52") (name "Net-(LED8-K)") (class "Default")
      (node (ref "LED8") (pin "2") (pinfunction "K_2") (pintype "passive"))
      (node (ref "R18") (pin "1") (pinfunction "1_1") (pintype "passive"))
    )
    (net (code "53") (name "Net-(LED9-K)") (class "Default")
      (node (ref "LED9") (pin "2") (pinfunction "K_2") (pintype "passive"))
      (node (ref "R27") (pin "2") (pinfunction "2_2") (pintype "passive"))
    )
    (net (code "54") (name "Net-(LED10-K)") (class "Default")
      (node (ref "LED10") (pin "2") (pinfunction "K_2") (pintype "passive"))
      (node (ref "R28") (pin "2") (pinfunction "2_2") (pintype "passive"))
    )
    (net (code "55") (name "Net-(LED11-K)") (class "Default")
      (node (ref "LED11") (pin "2") (pinfunction "K_2") (pintype "passive"))
      (node (ref "R29") (pin "1") (pinfunction "1_1") (pintype "passive"))
    )
    (net (code "56") (name "Net-(LED12-K)") (class "Default")
      (node (ref "LED12") (pin "2") (pinfunction "K_2") (pintype "passive"))
      (node (ref "R32") (pin "1") (pinfunction "1_1") (pintype "passive"))
    )
    (net (code "57") (name "Net-(Q1-B)") (class "Default")
      (node (ref "Q1") (pin "3") (pinfunction "B_3") (pintype "passive"))
      (node (ref "R11") (pin "2") (pinfunction "2_2") (pintype "passive"))
    )
    (net (code "58") (name "Net-(Q2-B)") (class "Default")
      (node (ref "Q2") (pin "3") (pinfunction "B_3") (pintype "passive"))
      (node (ref "R12") (pin "2") (pinfunction "2_2") (pintype "passive"))
    )
    (net (code "59") (name "Net-(Q3-B)") (class "Default")
      (node (ref "Q3") (pin "3") (pinfunction "B_3") (pintype "passive"))
      (node (ref "R23") (pin "2") (pinfunction "2_2") (pintype "passive"))
    )
    (net (code "60") (name "Net-(Q4-B)") (class "Default")
      (node (ref "Q4") (pin "3") (pinfunction "B_3") (pintype "passive"))
      (node (ref "R24") (pin "2") (pinfunction "2_2") (pintype "passive"))
    )
    (net (code "61") (name "Net-(Q5-B)") (class "Default")
      (node (ref "Q5") (pin "3") (pinfunction "B_3") (pintype "passive"))
      (node (ref "R35") (pin "2") (pinfunction "2_2") (pintype "passive"))
    )
    (net (code "62") (name "Net-(Q6-B)") (class "Default")
      (node (ref "Q6") (pin "3") (pinfunction "B_3") (pintype "passive"))
      (node (ref "R36") (pin "2") (pinfunction "2_2") (pintype "passive"))
    )
    (net (code "63") (name "Net-(U1-A)") (class "Default")
      (node (ref "R9") (pin "2") (pinfunction "2_2") (pintype "passive"))
      (node (ref "U1") (pin "1") (pinfunction "A_1") (pintype "passive"))
    )
    (net (code "64") (name "Net-(U1-E)") (class "Default")
      (node (ref "R11") (pin "1") (pinfunction "1_1") (pintype "passive"))
      (node (ref "U1") (pin "3") (pinfunction "E_3") (pintype "passive"))
    )
    (net (code "65") (name "Net-(U2-A)") (class "Default")
      (node (ref "R10") (pin "2") (pinfunction "2_2") (pintype "passive"))
      (node (ref "U2") (pin "1") (pinfunction "A_1") (pintype "passive"))
    )
    (net (code "66") (name "Net-(U2-E)") (class "Default")
      (node (ref "R12") (pin "1") (pinfunction "1_1") (pintype "passive"))
      (node (ref "U2") (pin "3") (pinfunction "E_3") (pintype "passive"))
    )
    (net (code "67") (name "Net-(U3-A)") (class "Default")
      (node (ref "R21") (pin "2") (pinfunction "2_2") (pintype "passive"))
      (node (ref "U3") (pin "1") (pinfunction "A_1") (pintype "passive"))
    )
    (net (code "68") (name "Net-(U3-E)") (class "Default")
      (node (ref "R23") (pin "1") (pinfunction "1_1") (pintype "passive"))
      (node (ref "U3") (pin "3") (pinfunction "E_3") (pintype "passive"))
    )
    (net (code "69") (name "Net-(U4-A)") (class "Default")
      (node (ref "R22") (pin "2") (pinfunction "2_2") (pintype "passive"))
      (node (ref "U4") (pin "1") (pinfunction "A_1") (pintype "passive"))
    )
    (net (code "70") (name "Net-(U4-E)") (class "Default")
      (node (ref "R24") (pin "1") (pinfunction "1_1") (pintype "passive"))
      (node (ref "U4") (pin "3") (pinfunction "E_3") (pintype "passive"))
    )
    (net (code "71") (name "Net-(U5-A)") (class "Default")
      (node (ref "R33") (pin "2") (pinfunction "2_2") (pintype "passive"))
      (node (ref "U5") (pin "1") (pinfunction "A_1") (pintype "passive"))
    )
    (net (code "72") (name "Net-(U5-E)") (class "Default")
      (node (ref "R35") (pin "1") (pinfunction "1_1") (pintype "passive"))
      (node (ref "U5") (pin "3") (pinfunction "E_3") (pintype "passive"))
    )
    (net (code "73") (name "Net-(U6-A)") (class "Default")
      (node (ref "R34") (pin "2") (pinfunction "2_2") (pintype "passive"))
      (node (ref "U6") (pin "1") (pinfunction "A_1") (pintype "passive"))
    )
    (net (code "74") (name "Net-(U6-E)") (class "Default")
      (node (ref "R36") (pin "1") (pinfunction "1_1") (pintype "passive"))
      (node (ref "U6") (pin "3") (pinfunction "E_3") (pintype "passive"))
    )
    (net (code "75") (name "Net-(UN1-IN)") (class "Default")
      (node (ref "C3") (pin "1") (pinfunction "1_1") (pintype "passive"))
      (node (ref "P1") (pin "1") (pinfunction "1_1") (pintype "passive"))
      (node (ref "UN1") (pin "1") (pinfunction "IN_1") (pintype "power_in"))
    )
    (net (code "76") (name "VCC5") (class "Default")
      (node (ref "B1") (pin "2") (pinfunction "VIN_2") (pintype "passive"))
      (node (ref "C2") (pin "1") (pinfunction "1_1") (pintype "passive"))
      (node (ref "C7") (pin "1") (pinfunction "1_1") (pintype "passive"))
      (node (ref "D1") (pin "2") (pinfunction "K_2") (pintype "passive"))
      (node (ref "D2") (pin "2") (pinfunction "K_2") (pintype "passive"))
      (node (ref "D3") (pin "2") (pinfunction "K_2") (pintype "passive"))
      (node (ref "D4") (pin "2") (pinfunction "K_2") (pintype "passive"))
      (node (ref "D5") (pin "2") (pinfunction "K_2") (pintype "passive"))
      (node (ref "D6") (pin "2") (pinfunction "K_2") (pintype "passive"))
      (node (ref "LED11") (pin "1") (pinfunction "A_1") (pintype "passive"))
      (node (ref "LED12") (pin "1") (pinfunction "A_1") (pintype "passive"))
      (node (ref "LED3") (pin "1") (pinfunction "A_1") (pintype "passive"))
      (node (ref "LED4") (pin "1") (pinfunction "A_1") (pintype "passive"))
      (node (ref "LED7") (pin "1") (pinfunction "A_1") (pintype "passive"))
      (node (ref "LED8") (pin "1") (pinfunction "A_1") (pintype "passive"))
      (node (ref "RL1") (pin "3") (pinfunction "3_3") (pintype "passive"))
      (node (ref "RL2") (pin "3") (pinfunction "3_3") (pintype "passive"))
      (node (ref "RL3") (pin "3") (pinfunction "3_3") (pintype "passive"))
      (node (ref "RL4") (pin "3") (pinfunction "3_3") (pintype "passive"))
      (node (ref "RL5") (pin "3") (pinfunction "3_3") (pintype "passive"))
      (node (ref "RL6") (pin "3") (pinfunction "3_3") (pintype "passive"))
      (node (ref "U1") (pin "4") (pinfunction "C_4") (pintype "passive"))
      (node (ref "U2") (pin "4") (pinfunction "C_4") (pintype "passive"))
      (node (ref "U3") (pin "4") (pinfunction "C_4") (pintype "passive"))
      (node (ref "U4") (pin "4") (pinfunction "C_4") (pintype "passive"))
      (node (ref "U5") (pin "4") (pinfunction "C_4") (pintype "passive"))
      (node (ref "U6") (pin "4") (pinfunction "C_4") (pintype "passive"))
      (node (ref "UN1") (pin "3") (pinfunction "OUT_3") (pintype "power_in"))
    )
    (net (code "77") (name "VCC5_ISO") (class "Default")
      (node (ref "B1") (pin "4") (pinfunction "+VO_4") (pintype "passive"))
      (node (ref "C16") (pin "3") (pinfunction "3_3") (pintype "passive"))
      (node (ref "C17") (pin "3") (pinfunction "3_3") (pintype "passive"))
      (node (ref "C18") (pin "3") (pinfunction "3_3") (pintype "passive"))
      (node (ref "C19") (pin "4") (pinfunction "4_4") (pintype "passive"))
      (node (ref "C6") (pin "1") (pinfunction "1_1") (pintype "passive"))
      (node (ref "LED1") (pin "1") (pinfunction "A_1") (pintype "passive"))
      (node (ref "LED10") (pin "1") (pinfunction "A_1") (pintype "passive"))
      (node (ref "LED2") (pin "1") (pinfunction "A_1") (pintype "passive"))
      (node (ref "LED5") (pin "1") (pinfunction "A_1") (pintype "passive"))
      (node (ref "LED6") (pin "1") (pinfunction "A_1") (pintype "passive"))
      (node (ref "LED9") (pin "1") (pinfunction "A_1") (pintype "passive"))
      (node (ref "R1") (pin "2") (pinfunction "2_2") (pintype "passive"))
      (node (ref "R13") (pin "2") (pinfunction "2_2") (pintype "passive"))
      (node (ref "R14") (pin "2") (pinfunction "2_2") (pintype "passive"))
      (node (ref "R2") (pin "2") (pinfunction "2_2") (pintype "passive"))
      (node (ref "R25") (pin "2") (pinfunction "2_2") (pintype "passive"))
      (node (ref "R26") (pin "2") (pinfunction "2_2") (pintype "passive"))
      (node (ref "U7") (pin "15") (pinfunction "VIN_15") (pintype "passive"))
    )
    (net (code "78") (name "VCC33_ISO") (class "Default")
      (node (ref "C10") (pin "3") (pinfunction "3_3") (pintype "passive"))
      (node (ref "C11") (pin "3") (pinfunction "3_3") (pintype "passive"))
      (node (ref "C14") (pin "3") (pinfunction "3_3") (pintype "passive"))
      (node (ref "C15") (pin "3") (pinfunction "3_3") (pintype "passive"))
      (node (ref "U7") (pin "16") (pinfunction "3V3_16") (pintype "passive"))
    )
    (net (code "79") (name "unconnected-(RL1-Pad2)") (class "Default")
      (node (ref "RL1") (pin "2") (pinfunction "2_2") (pintype "passive+no_connect"))
    )
    (net (code "80") (name "unconnected-(RL2-Pad2)") (class "Default")
      (node (ref "RL2") (pin "2") (pinfunction "2_2") (pintype "passive+no_connect"))
    )
    (net (code "81") (name "unconnected-(RL3-Pad2)") (class "Default")
      (node (ref "RL3") (pin "2") (pinfunction "2_2") (pintype "passive+no_connect"))
    )
    (net (code "82") (name "unconnected-(RL4-Pad2)") (class "Default")
      (node (ref "RL4") (pin "2") (pinfunction "2_2") (pintype "passive+no_connect"))
    )
    (net (code "83") (name "unconnected-(RL5-Pad2)") (class "Default")
      (node (ref "RL5") (pin "2") (pinfunction "2_2") (pintype "passive+no_connect"))
    )
    (net (code "84") (name "unconnected-(RL6-Pad2)") (class "Default")
      (node (ref "RL6") (pin "2") (pinfunction "2_2") (pintype "passive+no_connect"))
    )
    (net (code "85") (name "unconnected-(U7-D2-Pad19)") (class "Default")
      (node (ref "U7") (pin "19") (pinfunction "D2_19") (pintype "passive+no_connect"))
    )
    (net (code "86") (name "unconnected-(U7-EN-Pad1)") (class "Default")
      (node (ref "U7") (pin "1") (pinfunction "EN_1") (pintype "passive+no_connect"))
    )
    (net (code "87") (name "unconnected-(U7-RX0-Pad27)") (class "Default")
      (node (ref "U7") (pin "27") (pinfunction "RX0_27") (pintype "passive+no_connect"))
    )
    (net (code "88") (name "unconnected-(U7-TX0-Pad28)") (class "Default")
      (node (ref "U7") (pin "28") (pinfunction "TX0_28") (pintype "passive+no_connect"))
    )
  )
)
